# BrauV2_TopLevel.net
KiCad netlist of a schematic drawn in Altium Designer
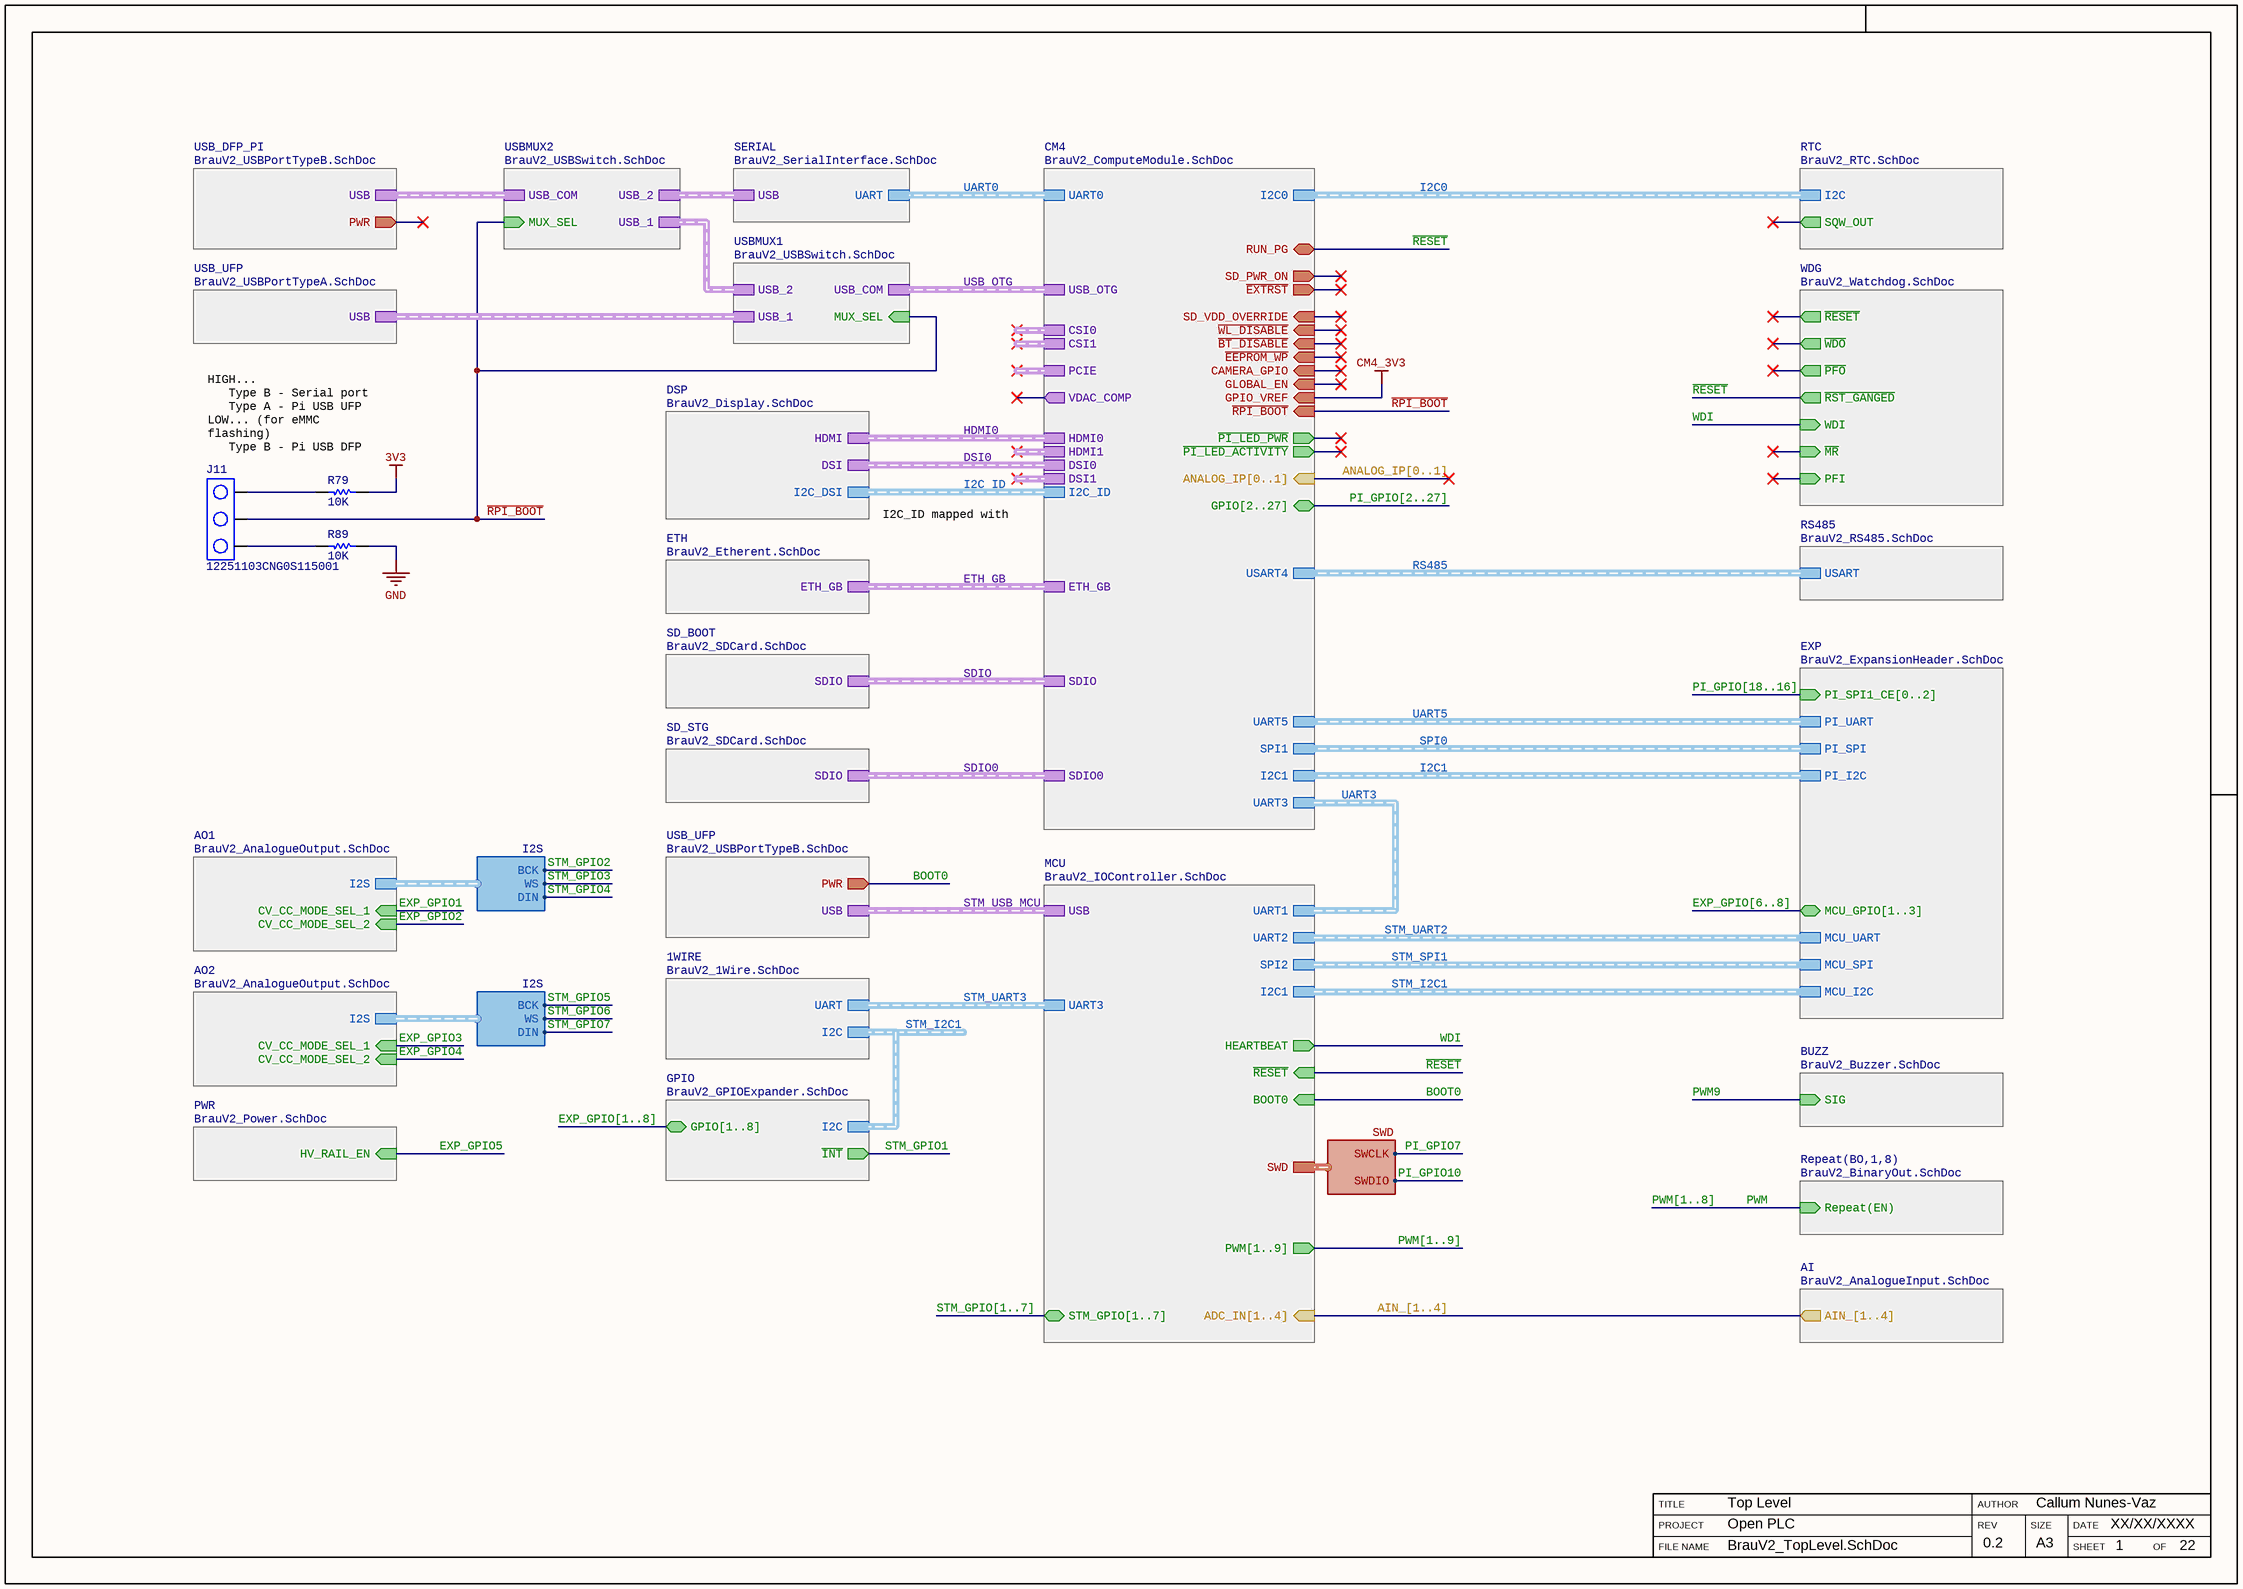
[diagram p0: BrauV2_TopLevel.SchDoc]

(export (version "E")
  (design (tool "Eeschema 10.0.6"))
  (components
    (comp (ref "J11")
      (value "12251103CNG0S115001")
      (footprint "Header_3POS")
      (description "Pin Header 3 1 right-angle，180degrees 2.54mm Through Hole,P=2.54mm Pin Header & Female Header RoHS")
      (libsource (lib "BrauV2_Connector") (part "3-way Jumper"))
    )
    (comp (ref "R79")
      (value "RC0402FR-0710KL")
      (footprint "SMD_RES_0402(1005)_N")
      (description "10kΩ ±1% 1/16W ±100ppm/℃ 0402 Chip Resistor - Surface Mount RoHS")
      (fields (field (name "TOLERANCE") "1%") (field (name "RESISTANCE") "10K"))
      (libsource (lib "BrauV2_Resistor") (part "10K 0402 1% 1/16W"))
    )
    (comp (ref "R89")
      (value "RC0402FR-0710KL")
      (footprint "SMD_RES_0402(1005)_N")
      (description "10kΩ ±1% 1/16W ±100ppm/℃ 0402 Chip Resistor - Surface Mount RoHS")
      (fields (field (name "TOLERANCE") "1%") (field (name "RESISTANCE") "10K"))
      (libsource (lib "BrauV2_Resistor") (part "10K 0402 1% 1/16W"))
    )
  )
  (nets
    (net (code "137") (name "/~{RPI_BOOT}") (class "Default")
      (node (ref "J11") (pin "2") (pinfunction "2_2") (pintype "passive"))
    )
    (net (code "140") (name "3V3") (class "Default")
      (node (ref "R79") (pin "2") (pinfunction "2_2") (pintype "passive"))
    )
    (net (code "142") (name "GND") (class "Default")
      (node (ref "R89") (pin "1") (pinfunction "1_1") (pintype "passive"))
    )
    (net (code "143") (name "Net-(J11-Pad1)") (class "Default")
      (node (ref "J11") (pin "1") (pinfunction "1_1") (pintype "passive"))
      (node (ref "R79") (pin "1") (pinfunction "1_1") (pintype "passive"))
    )
    (net (code "144") (name "Net-(J11-Pad3)") (class "Default")
      (node (ref "J11") (pin "3") (pinfunction "3_3") (pintype "passive"))
      (node (ref "R89") (pin "2") (pinfunction "2_2") (pintype "passive"))
    )
  )
)
